# Schematic_v2_2.net
KiCad netlist of a schematic drawn in EAGLE
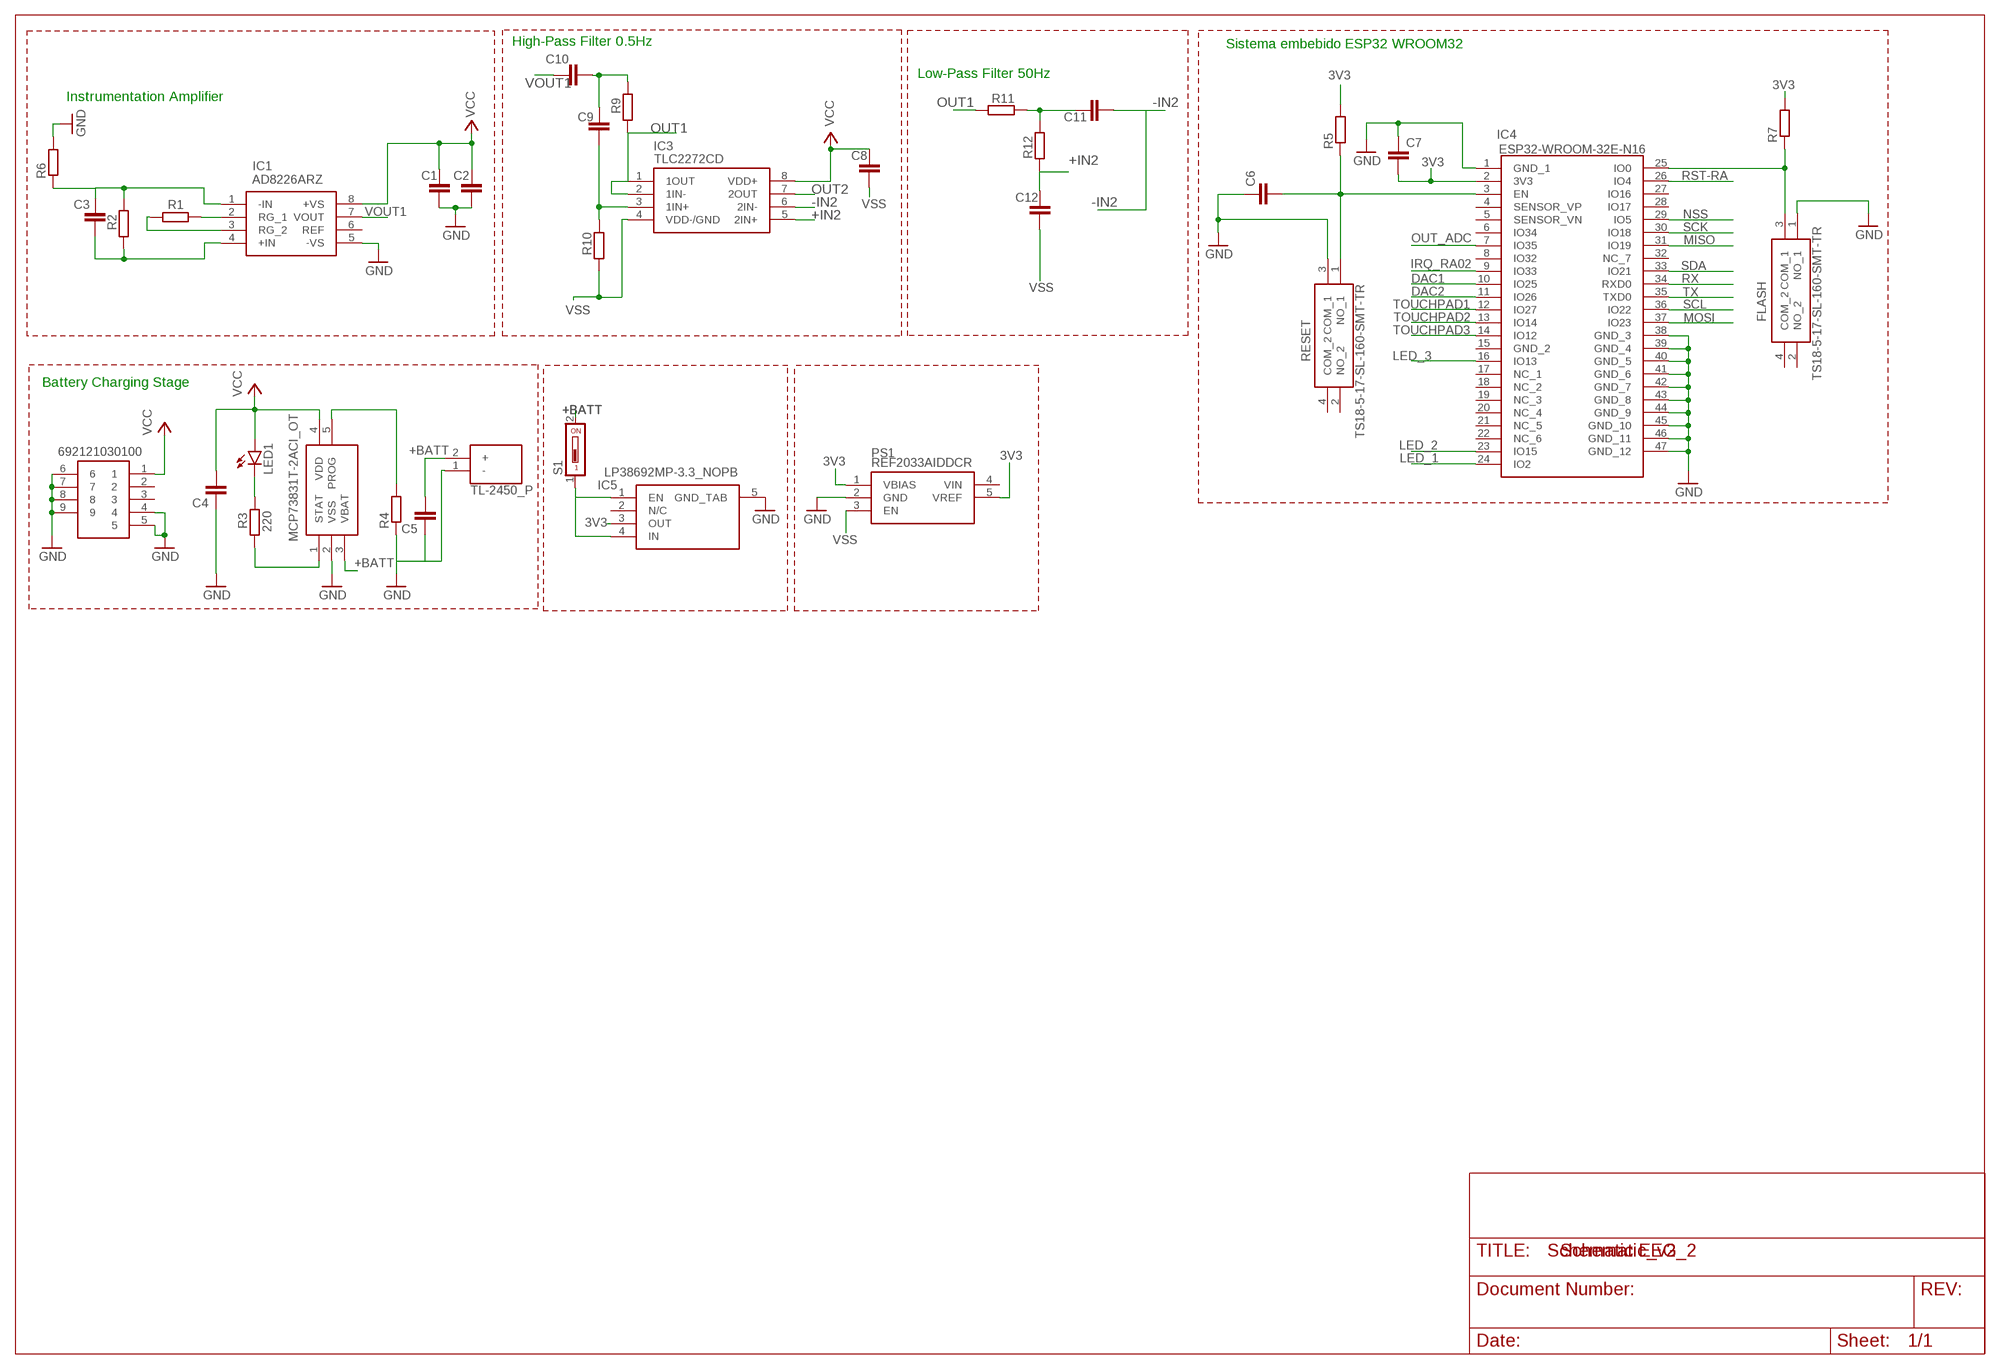
[diagram p0: schematic, sheet 1]

(export (version "E")
  (design (tool "Eeschema 10.0.6"))
  (components
    (comp (ref "BT1")
      (value "TL-2450_P")
      (footprint "eagle-import:TL2450P")
      (fields (field (name "ARROW_PART_NUMBER") "TL-2450/P"))
      (libsource (lib "eagle-import") (part "TL-2450_P"))
    )
    (comp (ref "C1")
      (value "C-EUC0805")
      (footprint "eagle-import:C0805")
      (libsource (lib "eagle-import") (part "C-EUC0805"))
    )
    (comp (ref "C2")
      (value "C-EUC0805")
      (footprint "eagle-import:C0805")
      (libsource (lib "eagle-import") (part "C-EUC0805"))
    )
    (comp (ref "C3")
      (value "C-EUC0805")
      (footprint "eagle-import:C0805")
      (libsource (lib "eagle-import") (part "C-EUC0805"))
    )
    (comp (ref "C4")
      (value "C-EUC0805")
      (footprint "eagle-import:C0805")
      (libsource (lib "eagle-import") (part "C-EUC0805"))
    )
    (comp (ref "C5")
      (value "C-EUC0805")
      (footprint "eagle-import:C0805")
      (libsource (lib "eagle-import") (part "C-EUC0805"))
    )
    (comp (ref "C6")
      (value "C-EUC0805")
      (footprint "eagle-import:C0805")
      (libsource (lib "eagle-import") (part "C-EUC0805"))
    )
    (comp (ref "C7")
      (value "C-EUC0805")
      (footprint "eagle-import:C0805")
      (libsource (lib "eagle-import") (part "C-EUC0805"))
    )
    (comp (ref "C8")
      (value "C-EUC0805")
      (footprint "eagle-import:C0805")
      (libsource (lib "eagle-import") (part "C-EUC0805"))
    )
    (comp (ref "C9")
      (value "C-EUC0805")
      (footprint "eagle-import:C0805")
      (libsource (lib "eagle-import") (part "C-EUC0805"))
    )
    (comp (ref "C10")
      (value "C-EUC0805")
      (footprint "eagle-import:C0805")
      (libsource (lib "eagle-import") (part "C-EUC0805"))
    )
    (comp (ref "C11")
      (value "C-EUC0805")
      (footprint "eagle-import:C0805")
      (libsource (lib "eagle-import") (part "C-EUC0805"))
    )
    (comp (ref "C12")
      (value "C-EUC0805")
      (footprint "eagle-import:C0805")
      (libsource (lib "eagle-import") (part "C-EUC0805"))
    )
    (comp (ref "FLASH")
      (value "TS18-5-17-SL-160-SMT-TR")
      (footprint "eagle-import:TS18517SL160SMTTR")
      (fields (field (name "MOUSER_PART_NUMBER") "179-TS18517SL160SMTT"))
      (libsource (lib "eagle-import") (part "TS18-5-17-SL-160-SMT-TR"))
    )
    (comp (ref "IC1")
      (value "AD8226ARZ")
      (footprint "eagle-import:SOIC127P600X175-8N")
      (fields (field (name "MOUSER_PART_NUMBER") "584-AD8226ARZ"))
      (libsource (lib "eagle-import") (part "AD8226ARZ"))
    )
    (comp (ref "IC2")
      (value "MCP73831T-2ACI_OT")
      (footprint "eagle-import:SOT95P270X145-5N")
      (fields
        (field (name "ARROW_PART_NUMBER") "MCP73831T-2ACI/OT")
        (field (name "MOUSER_PART_NUMBER") "579-MCP73831T-2ACIOT")
      )
      (libsource (lib "eagle-import") (part "MCP73831T-2ACI_OT"))
    )
    (comp (ref "IC3")
      (value "TLC2272CD")
      (footprint "eagle-import:SOIC127P600X175-8N")
      (fields (field (name "MOUSER_PART_NUMBER") "595-TLC2272CD"))
      (libsource (lib "eagle-import") (part "TLC2272CD"))
    )
    (comp (ref "IC4")
      (value "ESP32-WROOM-32E-N16")
      (footprint "eagle-import:ESP32WROOM32EN16")
      (fields (field (name "MOUSER_PART_NUMBER") "356-ESP32WRM32E128PH"))
      (libsource (lib "eagle-import") (part "ESP32-WROOM-32E-N16"))
    )
    (comp (ref "IC5")
      (value "LP38692MP-3.3_NOPB")
      (footprint "eagle-import:SOT150P700X180-5N")
      (fields
        (field (name "MANUFACTURER_PART_NUMBER") "LP38692MP-3.3/NOPB")
        (field (name "MOUSER_PART_NUMBER") "926-LP38692MP3.3NOPB")
      )
      (libsource (lib "eagle-import") (part "LP38692MP-3.3_NOPB"))
    )
    (comp (ref "J1")
      (value "692121030100")
      (footprint "eagle-import:692121030100")
      (fields (field (name "MOUSER_PART_NUMBER") "710-692121030100"))
      (libsource (lib "eagle-import") (part "692121030100"))
    )
    (comp (ref "LED1")
      (value "LEDCHIP-LED0805")
      (footprint "eagle-import:CHIP-LED0805")
      (libsource (lib "eagle-import") (part "LEDCHIP-LED0805"))
    )
    (comp (ref "PS1")
      (value "REF2033AIDDCR")
      (footprint "eagle-import:SOT95P280X110-5N")
      (fields (field (name "MOUSER_PART_NUMBER") "595-REF2033AIDDCR"))
      (libsource (lib "eagle-import") (part "REF2033AIDDCR"))
    )
    (comp (ref "R1")
      (value "R-EU_R0805")
      (footprint "eagle-import:R0805")
      (libsource (lib "eagle-import") (part "R-EU_R0805"))
    )
    (comp (ref "R2")
      (value "R-EU_R0805")
      (footprint "eagle-import:R0805")
      (libsource (lib "eagle-import") (part "R-EU_R0805"))
    )
    (comp (ref "R3")
      (value "220")
      (footprint "eagle-import:R0805")
      (libsource (lib "eagle-import") (part "R-EU_R0805"))
    )
    (comp (ref "R4")
      (value "R-EU_R0805")
      (footprint "eagle-import:R0805")
      (libsource (lib "eagle-import") (part "R-EU_R0805"))
    )
    (comp (ref "R5")
      (value "R-EU_R0805")
      (footprint "eagle-import:R0805")
      (libsource (lib "eagle-import") (part "R-EU_R0805"))
    )
    (comp (ref "R6")
      (value "R-EU_R0805")
      (footprint "eagle-import:R0805")
      (libsource (lib "eagle-import") (part "R-EU_R0805"))
    )
    (comp (ref "R7")
      (value "R-EU_R0805")
      (footprint "eagle-import:R0805")
      (libsource (lib "eagle-import") (part "R-EU_R0805"))
    )
    (comp (ref "R9")
      (value "R-EU_R0805")
      (footprint "eagle-import:R0805")
      (libsource (lib "eagle-import") (part "R-EU_R0805"))
    )
    (comp (ref "R10")
      (value "R-EU_R0805")
      (footprint "eagle-import:R0805")
      (libsource (lib "eagle-import") (part "R-EU_R0805"))
    )
    (comp (ref "R11")
      (value "R-EU_R0805")
      (footprint "eagle-import:R0805")
      (libsource (lib "eagle-import") (part "R-EU_R0805"))
    )
    (comp (ref "R12")
      (value "R-EU_R0805")
      (footprint "eagle-import:R0805")
      (libsource (lib "eagle-import") (part "R-EU_R0805"))
    )
    (comp (ref "RESET")
      (value "TS18-5-17-SL-160-SMT-TR")
      (footprint "eagle-import:TS18517SL160SMTTR")
      (fields (field (name "MOUSER_PART_NUMBER") "179-TS18517SL160SMTT"))
      (libsource (lib "eagle-import") (part "TS18-5-17-SL-160-SMT-TR"))
    )
    (comp (ref "S1")
      (value "DS01")
      (footprint "eagle-import:DS-01")
      (libsource (lib "eagle-import") (part "DS01"))
    )
  )
  (nets
    (net (code "1") (name "/+BATT") (class "Default")
      (node (ref "BT1") (pin "2") (pinfunction "+_2") (pintype "bidirectional"))
      (node (ref "C5") (pin "2") (pinfunction "2_2") (pintype "passive"))
      (node (ref "IC2") (pin "3") (pinfunction "VBAT_3") (pintype "bidirectional"))
      (node (ref "S1") (pin "2") (pinfunction "2_2") (pintype "passive"))
    )
    (net (code "2") (name "/+IN2") (class "Default")
      (node (ref "C12") (pin "1") (pinfunction "1_1") (pintype "passive"))
      (node (ref "IC3") (pin "5") (pinfunction "2IN+_5") (pintype "bidirectional"))
      (node (ref "R12") (pin "1") (pinfunction "1_1") (pintype "passive"))
    )
    (net (code "3") (name "/-IN2") (class "Default")
      (node (ref "C11") (pin "2") (pinfunction "2_2") (pintype "passive"))
      (node (ref "IC3") (pin "6") (pinfunction "2IN-_6") (pintype "bidirectional"))
    )
    (net (code "4") (name "/3V3") (class "Default")
      (node (ref "C7") (pin "2") (pinfunction "2_2") (pintype "passive"))
      (node (ref "IC4") (pin "2") (pinfunction "3V3_2") (pintype "bidirectional"))
      (node (ref "IC5") (pin "3") (pinfunction "OUT_3") (pintype "output"))
      (node (ref "PS1") (pin "1") (pinfunction "VBIAS_1") (pintype "output"))
      (node (ref "PS1") (pin "5") (pinfunction "VREF_5") (pintype "output"))
      (node (ref "R5") (pin "2") (pinfunction "2_2") (pintype "passive"))
      (node (ref "R7") (pin "2") (pinfunction "2_2") (pintype "passive"))
    )
    (net (code "5") (name "/DAC1") (class "Default")
      (node (ref "IC4") (pin "10") (pinfunction "IO25_10") (pintype "bidirectional"))
    )
    (net (code "6") (name "/DAC2") (class "Default")
      (node (ref "IC4") (pin "11") (pinfunction "IO26_11") (pintype "bidirectional"))
    )
    (net (code "7") (name "/IRQ_RA02") (class "Default")
      (node (ref "IC4") (pin "9") (pinfunction "IO33_9") (pintype "bidirectional"))
    )
    (net (code "8") (name "/LED_1") (class "Default")
      (node (ref "IC4") (pin "24") (pinfunction "IO2_24") (pintype "bidirectional"))
    )
    (net (code "9") (name "/LED_2") (class "Default")
      (node (ref "IC4") (pin "23") (pinfunction "IO15_23") (pintype "bidirectional"))
    )
    (net (code "10") (name "/LED_3") (class "Default")
      (node (ref "IC4") (pin "16") (pinfunction "IO13_16") (pintype "bidirectional"))
    )
    (net (code "11") (name "/MISO") (class "Default")
      (node (ref "IC4") (pin "31") (pinfunction "IO19_31") (pintype "bidirectional"))
    )
    (net (code "12") (name "/MOSI") (class "Default")
      (node (ref "IC4") (pin "37") (pinfunction "IO23_37") (pintype "bidirectional"))
    )
    (net (code "13") (name "/NSS") (class "Default")
      (node (ref "IC4") (pin "29") (pinfunction "IO5_29") (pintype "bidirectional"))
    )
    (net (code "14") (name "/OUT1") (class "Default")
      (node (ref "IC3") (pin "1") (pinfunction "1OUT_1") (pintype "bidirectional"))
      (node (ref "IC3") (pin "2") (pinfunction "1IN-_2") (pintype "bidirectional"))
      (node (ref "R11") (pin "1") (pinfunction "1_1") (pintype "passive"))
      (node (ref "R9") (pin "1") (pinfunction "1_1") (pintype "passive"))
    )
    (net (code "15") (name "/OUT2") (class "Default")
      (node (ref "C10") (pin "2") (pinfunction "2_2") (pintype "passive"))
      (node (ref "C9") (pin "1") (pinfunction "1_1") (pintype "passive"))
      (node (ref "IC3") (pin "7") (pinfunction "2OUT_7") (pintype "bidirectional"))
      (node (ref "R9") (pin "2") (pinfunction "2_2") (pintype "passive"))
    )
    (net (code "16") (name "/OUT_ADC") (class "Default")
      (node (ref "IC4") (pin "7") (pinfunction "IO35_7") (pintype "bidirectional"))
    )
    (net (code "17") (name "/RST-RA") (class "Default")
      (node (ref "IC4") (pin "26") (pinfunction "IO4_26") (pintype "bidirectional"))
    )
    (net (code "18") (name "/RX") (class "Default")
      (node (ref "IC4") (pin "34") (pinfunction "RXD0_34") (pintype "bidirectional"))
    )
    (net (code "19") (name "/SCK") (class "Default")
      (node (ref "IC4") (pin "30") (pinfunction "IO18_30") (pintype "bidirectional"))
    )
    (net (code "20") (name "/SCL") (class "Default")
      (node (ref "IC4") (pin "36") (pinfunction "IO22_36") (pintype "bidirectional"))
    )
    (net (code "21") (name "/SDA") (class "Default")
      (node (ref "IC4") (pin "33") (pinfunction "IO21_33") (pintype "bidirectional"))
    )
    (net (code "22") (name "/TOUCHPAD1") (class "Default")
      (node (ref "IC4") (pin "12") (pinfunction "IO27_12") (pintype "bidirectional"))
    )
    (net (code "23") (name "/TOUCHPAD2") (class "Default")
      (node (ref "IC4") (pin "13") (pinfunction "IO14_13") (pintype "bidirectional"))
    )
    (net (code "24") (name "/TOUCHPAD3") (class "Default")
      (node (ref "IC4") (pin "14") (pinfunction "IO12_14") (pintype "bidirectional"))
    )
    (net (code "25") (name "/TX") (class "Default")
      (node (ref "IC4") (pin "35") (pinfunction "TXD0_35") (pintype "bidirectional"))
    )
    (net (code "26") (name "/VIN") (class "Default")
      (node (ref "PS1") (pin "4") (pinfunction "VIN_4") (pintype "power_in"))
    )
    (net (code "27") (name "/VOUT1") (class "Default")
      (node (ref "C10") (pin "1") (pinfunction "1_1") (pintype "passive"))
      (node (ref "IC1") (pin "7") (pinfunction "VOUT_7") (pintype "bidirectional"))
    )
    (net (code "28") (name "/VSS") (class "Default")
      (node (ref "C12") (pin "2") (pinfunction "2_2") (pintype "passive"))
      (node (ref "C8") (pin "2") (pinfunction "2_2") (pintype "passive"))
      (node (ref "IC3") (pin "4") (pinfunction "VDD-/GND_4") (pintype "bidirectional"))
      (node (ref "PS1") (pin "3") (pinfunction "EN_3") (pintype "bidirectional"))
      (node (ref "R10") (pin "1") (pinfunction "1_1") (pintype "passive"))
    )
    (net (code "29") (name "GND") (class "Default")
      (node (ref "C1") (pin "2") (pinfunction "2_2") (pintype "passive"))
      (node (ref "C2") (pin "2") (pinfunction "2_2") (pintype "passive"))
      (node (ref "C4") (pin "1") (pinfunction "1_1") (pintype "passive"))
      (node (ref "C6") (pin "1") (pinfunction "1_1") (pintype "passive"))
      (node (ref "C7") (pin "1") (pinfunction "1_1") (pintype "passive"))
      (node (ref "FLASH") (pin "1") (pinfunction "NO_1_1") (pintype "bidirectional"))
      (node (ref "IC1") (pin "5") (pinfunction "-VS_5") (pintype "bidirectional"))
      (node (ref "IC2") (pin "2") (pinfunction "VSS_2") (pintype "bidirectional"))
      (node (ref "IC4") (pin "1") (pinfunction "GND_1_1") (pintype "bidirectional"))
      (node (ref "IC4") (pin "38") (pinfunction "GND_3_38") (pintype "bidirectional"))
      (node (ref "IC4") (pin "39") (pinfunction "GND_4_39") (pintype "bidirectional"))
      (node (ref "IC4") (pin "40") (pinfunction "GND_5_40") (pintype "bidirectional"))
      (node (ref "IC4") (pin "41") (pinfunction "GND_6_41") (pintype "bidirectional"))
      (node (ref "IC4") (pin "42") (pinfunction "GND_7_42") (pintype "bidirectional"))
      (node (ref "IC4") (pin "43") (pinfunction "GND_8_43") (pintype "bidirectional"))
      (node (ref "IC4") (pin "44") (pinfunction "GND_9_44") (pintype "bidirectional"))
      (node (ref "IC4") (pin "45") (pinfunction "GND_10_45") (pintype "bidirectional"))
      (node (ref "IC4") (pin "46") (pinfunction "GND_11_46") (pintype "bidirectional"))
      (node (ref "IC4") (pin "47") (pinfunction "GND_12_47") (pintype "bidirectional"))
      (node (ref "IC5") (pin "5") (pinfunction "GND_TAB_5") (pintype "power_in"))
      (node (ref "J1") (pin "4") (pinfunction "4_4") (pintype "bidirectional"))
      (node (ref "J1") (pin "5") (pinfunction "5_5") (pintype "bidirectional"))
      (node (ref "J1") (pin "6") (pinfunction "6_6") (pintype "bidirectional"))
      (node (ref "J1") (pin "7") (pinfunction "7_7") (pintype "bidirectional"))
      (node (ref "J1") (pin "8") (pinfunction "8_8") (pintype "bidirectional"))
      (node (ref "J1") (pin "9") (pinfunction "9_9") (pintype "bidirectional"))
      (node (ref "PS1") (pin "2") (pinfunction "GND_2") (pintype "power_in"))
      (node (ref "R4") (pin "1") (pinfunction "1_1") (pintype "passive"))
      (node (ref "R6") (pin "2") (pinfunction "2_2") (pintype "passive"))
      (node (ref "RESET") (pin "3") (pinfunction "COM_1_3") (pintype "bidirectional"))
    )
    (net (code "30") (name "Net-(C11-Pad1)") (class "Default")
      (node (ref "C11") (pin "1") (pinfunction "1_1") (pintype "passive"))
      (node (ref "R11") (pin "2") (pinfunction "2_2") (pintype "passive"))
      (node (ref "R12") (pin "2") (pinfunction "2_2") (pintype "passive"))
    )
    (net (code "31") (name "Net-(FLASH-COM_1)") (class "Default")
      (node (ref "FLASH") (pin "3") (pinfunction "COM_1_3") (pintype "bidirectional"))
      (node (ref "IC4") (pin "25") (pinfunction "IO0_25") (pintype "bidirectional"))
      (node (ref "R7") (pin "1") (pinfunction "1_1") (pintype "passive"))
    )
    (net (code "32") (name "Net-(IC1-+IN)") (class "Default")
      (node (ref "C3") (pin "2") (pinfunction "2_2") (pintype "passive"))
      (node (ref "IC1") (pin "4") (pinfunction "+IN_4") (pintype "bidirectional"))
      (node (ref "R2") (pin "1") (pinfunction "1_1") (pintype "passive"))
    )
    (net (code "33") (name "Net-(IC1--IN)") (class "Default")
      (node (ref "C3") (pin "1") (pinfunction "1_1") (pintype "passive"))
      (node (ref "IC1") (pin "1") (pinfunction "-IN_1") (pintype "bidirectional"))
      (node (ref "R2") (pin "2") (pinfunction "2_2") (pintype "passive"))
      (node (ref "R6") (pin "1") (pinfunction "1_1") (pintype "passive"))
    )
    (net (code "34") (name "Net-(IC1-RG_1)") (class "Default")
      (node (ref "IC1") (pin "2") (pinfunction "RG_1_2") (pintype "bidirectional"))
      (node (ref "R1") (pin "2") (pinfunction "2_2") (pintype "passive"))
    )
    (net (code "35") (name "Net-(IC1-RG_2)") (class "Default")
      (node (ref "IC1") (pin "3") (pinfunction "RG_2_3") (pintype "bidirectional"))
      (node (ref "R1") (pin "1") (pinfunction "1_1") (pintype "passive"))
    )
    (net (code "36") (name "Net-(IC2-PROG)") (class "Default")
      (node (ref "IC2") (pin "5") (pinfunction "PROG_5") (pintype "bidirectional"))
      (node (ref "R4") (pin "2") (pinfunction "2_2") (pintype "passive"))
    )
    (net (code "37") (name "Net-(IC2-STAT)") (class "Default")
      (node (ref "IC2") (pin "1") (pinfunction "STAT_1") (pintype "bidirectional"))
      (node (ref "R3") (pin "1") (pinfunction "1_1") (pintype "passive"))
    )
    (net (code "38") (name "Net-(IC3-1IN+)") (class "Default")
      (node (ref "C9") (pin "2") (pinfunction "2_2") (pintype "passive"))
      (node (ref "IC3") (pin "3") (pinfunction "1IN+_3") (pintype "bidirectional"))
      (node (ref "R10") (pin "2") (pinfunction "2_2") (pintype "passive"))
    )
    (net (code "39") (name "Net-(IC4-EN)") (class "Default")
      (node (ref "C6") (pin "2") (pinfunction "2_2") (pintype "passive"))
      (node (ref "IC4") (pin "3") (pinfunction "EN_3") (pintype "bidirectional"))
      (node (ref "R5") (pin "1") (pinfunction "1_1") (pintype "passive"))
      (node (ref "RESET") (pin "1") (pinfunction "NO_1_1") (pintype "bidirectional"))
    )
    (net (code "40") (name "Net-(IC5-IN)") (class "Default")
      (node (ref "IC5") (pin "4") (pinfunction "IN_4") (pintype "input"))
      (node (ref "S1") (pin "1") (pinfunction "1_1") (pintype "passive"))
    )
    (net (code "41") (name "Net-(LED1-PadC)") (class "Default")
      (node (ref "LED1") (pin "C") (pinfunction "C_C") (pintype "passive"))
      (node (ref "R3") (pin "2") (pinfunction "2_2") (pintype "passive"))
    )
    (net (code "42") (name "VCC") (class "Default")
      (node (ref "C1") (pin "1") (pinfunction "1_1") (pintype "passive"))
      (node (ref "C2") (pin "1") (pinfunction "1_1") (pintype "passive"))
      (node (ref "C4") (pin "2") (pinfunction "2_2") (pintype "passive"))
      (node (ref "C8") (pin "1") (pinfunction "1_1") (pintype "passive"))
      (node (ref "IC1") (pin "8") (pinfunction "+VS_8") (pintype "bidirectional"))
      (node (ref "IC2") (pin "4") (pinfunction "VDD_4") (pintype "bidirectional"))
      (node (ref "IC3") (pin "8") (pinfunction "VDD+_8") (pintype "bidirectional"))
      (node (ref "J1") (pin "1") (pinfunction "1_1") (pintype "bidirectional"))
      (node (ref "LED1") (pin "A") (pinfunction "A_A") (pintype "passive"))
    )
    (net (code "43") (name "unconnected-(BT1---Pad1)") (class "Default")
      (node (ref "BT1") (pin "1") (pinfunction "-_1") (pintype "bidirectional"))
    )
    (net (code "44") (name "unconnected-(C5-Pad1)") (class "Default")
      (node (ref "C5") (pin "1") (pinfunction "1_1") (pintype "passive"))
    )
    (net (code "45") (name "unconnected-(FLASH-COM_2-Pad4)") (class "Default")
      (node (ref "FLASH") (pin "4") (pinfunction "COM_2_4") (pintype "bidirectional"))
    )
    (net (code "46") (name "unconnected-(FLASH-NO_2-Pad2)") (class "Default")
      (node (ref "FLASH") (pin "2") (pinfunction "NO_2_2") (pintype "bidirectional"))
    )
    (net (code "47") (name "unconnected-(IC1-REF-Pad6)") (class "Default")
      (node (ref "IC1") (pin "6") (pinfunction "REF_6") (pintype "bidirectional"))
    )
    (net (code "48") (name "unconnected-(IC4-GND_2-Pad15)") (class "Default")
      (node (ref "IC4") (pin "15") (pinfunction "GND_2_15") (pintype "bidirectional"))
    )
    (net (code "49") (name "unconnected-(IC4-IO16-Pad27)") (class "Default")
      (node (ref "IC4") (pin "27") (pinfunction "IO16_27") (pintype "bidirectional"))
    )
    (net (code "50") (name "unconnected-(IC4-IO17-Pad28)") (class "Default")
      (node (ref "IC4") (pin "28") (pinfunction "IO17_28") (pintype "bidirectional"))
    )
    (net (code "51") (name "unconnected-(IC4-IO32-Pad8)") (class "Default")
      (node (ref "IC4") (pin "8") (pinfunction "IO32_8") (pintype "bidirectional"))
    )
    (net (code "52") (name "unconnected-(IC4-IO34-Pad6)") (class "Default")
      (node (ref "IC4") (pin "6") (pinfunction "IO34_6") (pintype "bidirectional"))
    )
    (net (code "53") (name "unconnected-(IC4-NC_1-Pad17)") (class "Default")
      (node (ref "IC4") (pin "17") (pinfunction "NC_1_17") (pintype "bidirectional"))
    )
    (net (code "54") (name "unconnected-(IC4-NC_2-Pad18)") (class "Default")
      (node (ref "IC4") (pin "18") (pinfunction "NC_2_18") (pintype "bidirectional"))
    )
    (net (code "55") (name "unconnected-(IC4-NC_3-Pad19)") (class "Default")
      (node (ref "IC4") (pin "19") (pinfunction "NC_3_19") (pintype "bidirectional"))
    )
    (net (code "56") (name "unconnected-(IC4-NC_4-Pad20)") (class "Default")
      (node (ref "IC4") (pin "20") (pinfunction "NC_4_20") (pintype "bidirectional"))
    )
    (net (code "57") (name "unconnected-(IC4-NC_5-Pad21)") (class "Default")
      (node (ref "IC4") (pin "21") (pinfunction "NC_5_21") (pintype "bidirectional"))
    )
    (net (code "58") (name "unconnected-(IC4-NC_6-Pad22)") (class "Default")
      (node (ref "IC4") (pin "22") (pinfunction "NC_6_22") (pintype "bidirectional"))
    )
    (net (code "59") (name "unconnected-(IC4-NC_7-Pad32)") (class "Default")
      (node (ref "IC4") (pin "32") (pinfunction "NC_7_32") (pintype "bidirectional"))
    )
    (net (code "60") (name "unconnected-(IC4-SENSOR_VN-Pad5)") (class "Default")
      (node (ref "IC4") (pin "5") (pinfunction "SENSOR_VN_5") (pintype "bidirectional"))
    )
    (net (code "61") (name "unconnected-(IC4-SENSOR_VP-Pad4)") (class "Default")
      (node (ref "IC4") (pin "4") (pinfunction "SENSOR_VP_4") (pintype "bidirectional"))
    )
    (net (code "62") (name "unconnected-(IC5-EN-Pad1)") (class "Default")
      (node (ref "IC5") (pin "1") (pinfunction "EN_1") (pintype "bidirectional"))
    )
    (net (code "63") (name "unconnected-(IC5-N{slash}C-Pad2)") (class "Default")
      (node (ref "IC5") (pin "2") (pinfunction "N/C_2") (pintype "no_connect"))
    )
    (net (code "64") (name "unconnected-(J1-Pad2)") (class "Default")
      (node (ref "J1") (pin "2") (pinfunction "2_2") (pintype "bidirectional"))
    )
    (net (code "65") (name "unconnected-(J1-Pad3)") (class "Default")
      (node (ref "J1") (pin "3") (pinfunction "3_3") (pintype "bidirectional"))
    )
    (net (code "66") (name "unconnected-(RESET-COM_2-Pad4)") (class "Default")
      (node (ref "RESET") (pin "4") (pinfunction "COM_2_4") (pintype "bidirectional"))
    )
    (net (code "67") (name "unconnected-(RESET-NO_2-Pad2)") (class "Default")
      (node (ref "RESET") (pin "2") (pinfunction "NO_2_2") (pintype "bidirectional"))
    )
  )
)
